# LilypadShield_wPower.net
KiCad netlist of a schematic drawn in EAGLE
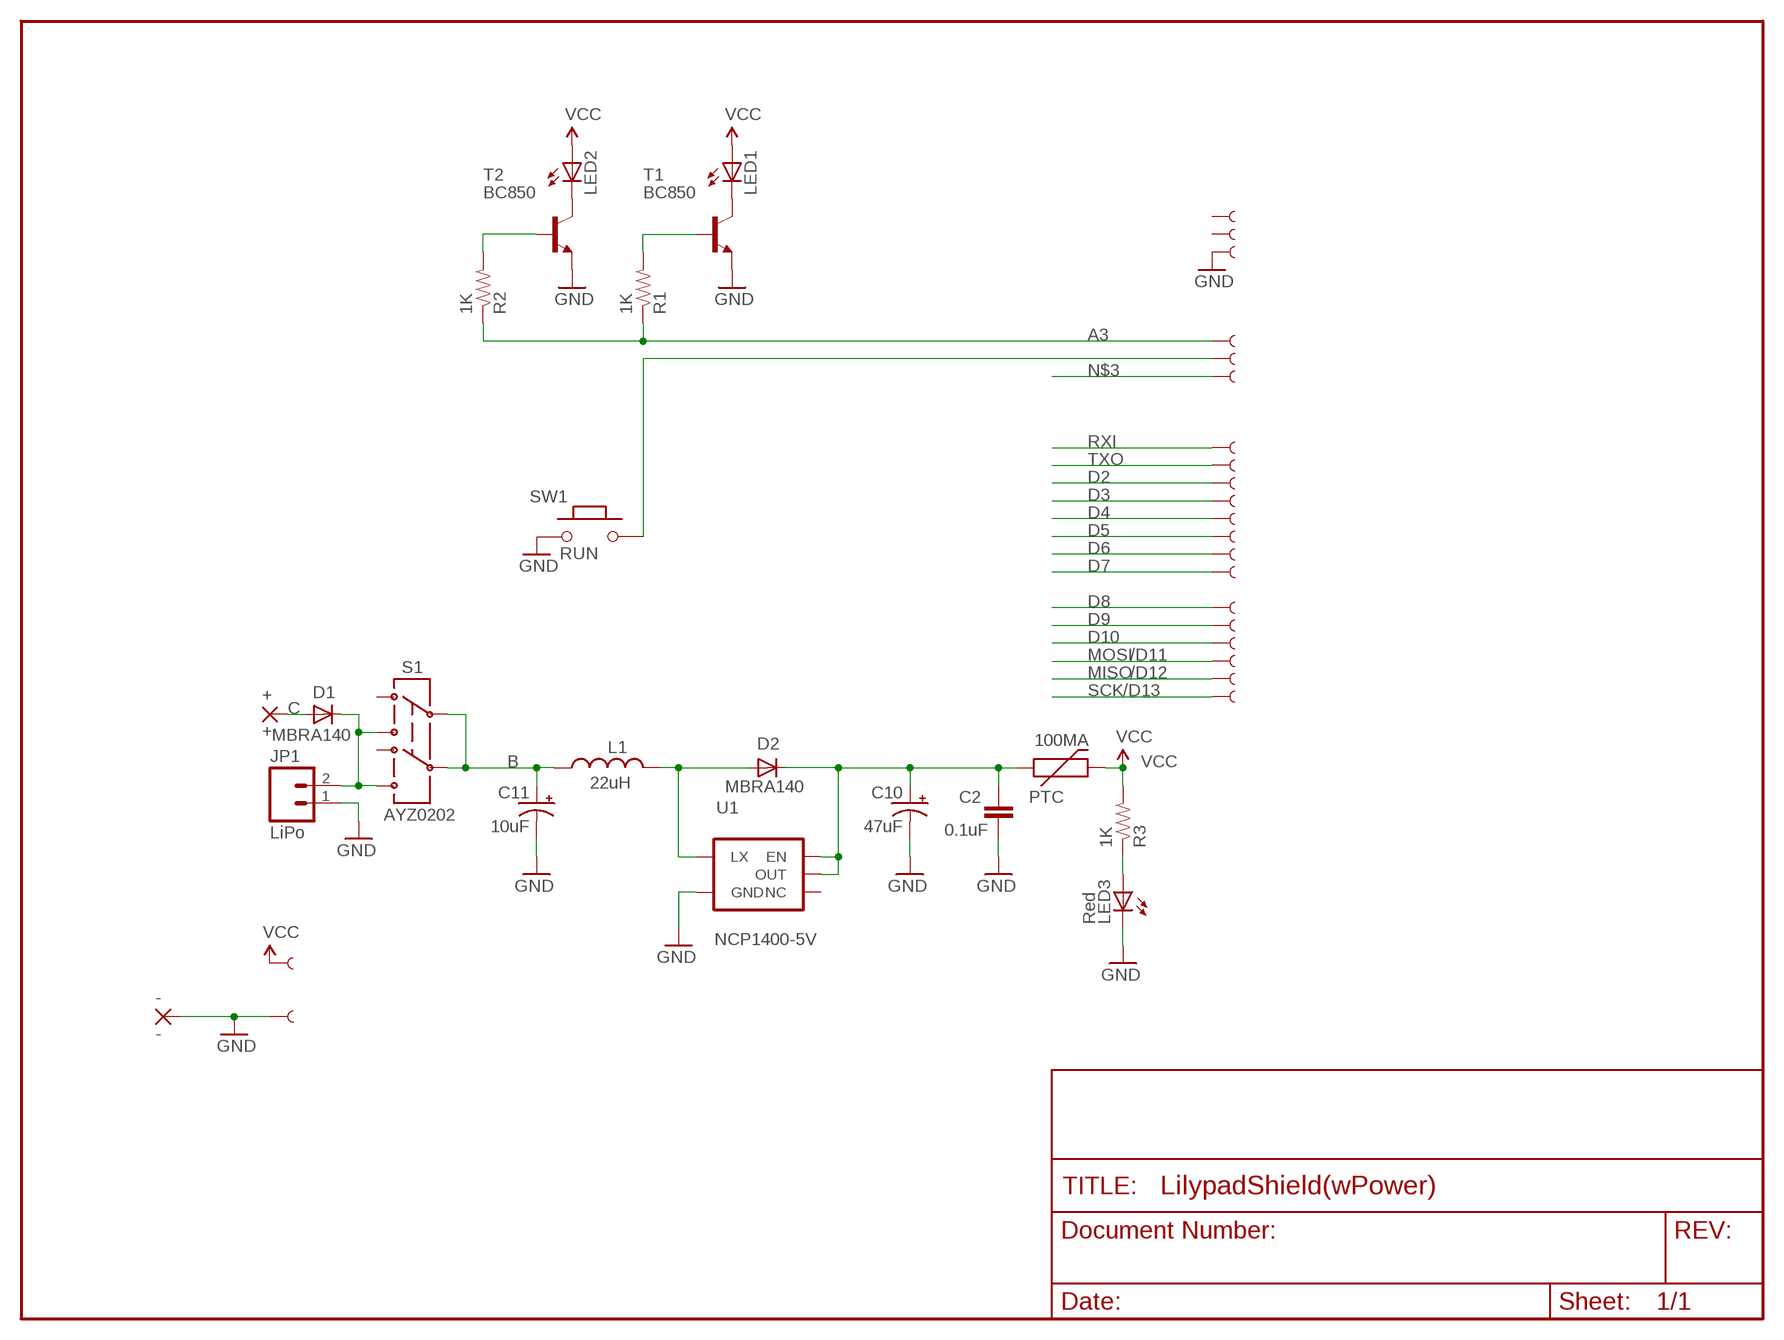
[diagram p0: schematic, sheet 1]

(export (version "E")
  (design (tool "Eeschema 10.0.6"))
  (components
    (comp (ref "+")
      (value "+")
      (footprint "eagle-import:1,6_0,8")
      (libsource (lib "eagle-import") (part "1,6/0,8"))
    )
    (comp (ref "-")
      (value "-")
      (footprint "eagle-import:1,6_0,8")
      (libsource (lib "eagle-import") (part "1,6/0,8"))
    )
    (comp (ref "100MA")
      (value "PTC")
      (footprint "eagle-import:PTC-1206")
      (libsource (lib "eagle-import") (part "PTCSMD"))
    )
    (comp (ref "C2")
      (value "0.1uF")
      (footprint "eagle-import:0603-CAP")
      (libsource (lib "eagle-import") (part "CAP0603-CAP"))
    )
    (comp (ref "C10")
      (value "47uF")
      (footprint "eagle-import:EIA3528-21")
      (libsource (lib "eagle-import") (part "CAP_POL2"))
    )
    (comp (ref "C11")
      (value "10uF")
      (footprint "eagle-import:CPOL_1206")
      (libsource (lib "eagle-import") (part "CAP_POL1206"))
    )
    (comp (ref "D1")
      (value "MBRA140")
      (footprint "eagle-import:SMA-DIODE")
      (libsource (lib "eagle-import") (part "DIODESMA"))
    )
    (comp (ref "D2")
      (value "MBRA140")
      (footprint "eagle-import:SMA-DIODE")
      (libsource (lib "eagle-import") (part "DIODESMA"))
    )
    (comp (ref "GND")
      (value "SEWTAP1")
      (footprint "eagle-import:SEWTAP")
      (libsource (lib "eagle-import") (part "SEWTAP1"))
    )
    (comp (ref "JP1")
      (value "LiPo")
      (footprint "eagle-import:JST-2-SMD")
      (libsource (lib "eagle-import") (part "M02-JST-2MM-SMT"))
    )
    (comp (ref "L1")
      (value "22uH")
      (footprint "eagle-import:CR54")
      (libsource (lib "eagle-import") (part "INDUCTORCR54"))
    )
    (comp (ref "LED1")
      (value "LED5MM")
      (footprint "eagle-import:LED5MM")
      (libsource (lib "eagle-import") (part "led_LED5MM"))
    )
    (comp (ref "LED2")
      (value "LED5MM")
      (footprint "eagle-import:LED5MM")
      (libsource (lib "eagle-import") (part "led_LED5MM"))
    )
    (comp (ref "LED3")
      (value "Red")
      (footprint "eagle-import:LED-1206")
      (libsource (lib "eagle-import") (part "LED1206"))
    )
    (comp (ref "R1")
      (value "1K")
      (footprint "eagle-import:0603-RES")
      (libsource (lib "eagle-import") (part "RESISTOR0603-RES"))
    )
    (comp (ref "R2")
      (value "1K")
      (footprint "eagle-import:0603-RES")
      (libsource (lib "eagle-import") (part "RESISTOR0603-RES"))
    )
    (comp (ref "R3")
      (value "1K")
      (footprint "eagle-import:0603-RES")
      (libsource (lib "eagle-import") (part "RESISTOR0603-RES"))
    )
    (comp (ref "S1")
      (value "AYZ0202")
      (footprint "eagle-import:AYZ0202")
      (libsource (lib "eagle-import") (part "AYZ0202"))
    )
    (comp (ref "SW1")
      (value "RUN")
      (footprint "eagle-import:157SW")
      (libsource (lib "eagle-import") (part "PB157"))
    )
    (comp (ref "T1")
      (value "BC850")
      (footprint "eagle-import:SOT23")
      (libsource (lib "eagle-import") (part "BC850"))
    )
    (comp (ref "T2")
      (value "BC850")
      (footprint "eagle-import:SOT23")
      (libsource (lib "eagle-import") (part "BC850"))
    )
    (comp (ref "U$4")
      (value "SEWTAP1")
      (footprint "eagle-import:SEWTAP")
      (libsource (lib "eagle-import") (part "SEWTAP1"))
    )
    (comp (ref "U$30")
      (value "SEWTAP1")
      (footprint "eagle-import:SEWTAP")
      (libsource (lib "eagle-import") (part "SEWTAP1"))
    )
    (comp (ref "U$31")
      (value "SEWTAP1")
      (footprint "eagle-import:SEWTAP")
      (libsource (lib "eagle-import") (part "SEWTAP1"))
    )
    (comp (ref "U$32")
      (value "SEWTAP1")
      (footprint "eagle-import:SEWTAP")
      (libsource (lib "eagle-import") (part "SEWTAP1"))
    )
    (comp (ref "U$33")
      (value "SEWTAP1")
      (footprint "eagle-import:SEWTAP")
      (libsource (lib "eagle-import") (part "SEWTAP1"))
    )
    (comp (ref "U$34")
      (value "SEWTAP1")
      (footprint "eagle-import:SEWTAP")
      (libsource (lib "eagle-import") (part "SEWTAP1"))
    )
    (comp (ref "U$35")
      (value "SEWTAP1")
      (footprint "eagle-import:SEWTAP")
      (libsource (lib "eagle-import") (part "SEWTAP1"))
    )
    (comp (ref "U$36")
      (value "SEWTAP1")
      (footprint "eagle-import:SEWTAP")
      (libsource (lib "eagle-import") (part "SEWTAP1"))
    )
    (comp (ref "U$37")
      (value "SEWTAP1")
      (footprint "eagle-import:SEWTAP")
      (libsource (lib "eagle-import") (part "SEWTAP1"))
    )
    (comp (ref "U$38")
      (value "SEWTAP1")
      (footprint "eagle-import:SEWTAP")
      (libsource (lib "eagle-import") (part "SEWTAP1"))
    )
    (comp (ref "U$39")
      (value "SEWTAP1")
      (footprint "eagle-import:SEWTAP")
      (libsource (lib "eagle-import") (part "SEWTAP1"))
    )
    (comp (ref "U$40")
      (value "SEWTAP1")
      (footprint "eagle-import:SEWTAP")
      (libsource (lib "eagle-import") (part "SEWTAP1"))
    )
    (comp (ref "U$41")
      (value "SEWTAP1")
      (footprint "eagle-import:SEWTAP")
      (libsource (lib "eagle-import") (part "SEWTAP1"))
    )
    (comp (ref "U$42")
      (value "SEWTAP1")
      (footprint "eagle-import:SEWTAP")
      (libsource (lib "eagle-import") (part "SEWTAP1"))
    )
    (comp (ref "U$43")
      (value "SEWTAP1")
      (footprint "eagle-import:SEWTAP")
      (libsource (lib "eagle-import") (part "SEWTAP1"))
    )
    (comp (ref "U$44")
      (value "SEWTAP1")
      (footprint "eagle-import:SEWTAP")
      (libsource (lib "eagle-import") (part "SEWTAP1"))
    )
    (comp (ref "U$45")
      (value "SEWTAP1")
      (footprint "eagle-import:SEWTAP")
      (libsource (lib "eagle-import") (part "SEWTAP1"))
    )
    (comp (ref "U$46")
      (value "SEWTAP1")
      (footprint "eagle-import:SEWTAP")
      (libsource (lib "eagle-import") (part "SEWTAP1"))
    )
    (comp (ref "U$47")
      (value "SEWTAP1")
      (footprint "eagle-import:SEWTAP")
      (libsource (lib "eagle-import") (part "SEWTAP1"))
    )
    (comp (ref "U$48")
      (value "SEWTAP1")
      (footprint "eagle-import:SEWTAP")
      (libsource (lib "eagle-import") (part "SEWTAP1"))
    )
    (comp (ref "U$51")
      (value "SEWTAP1")
      (footprint "eagle-import:SEWTAP")
      (libsource (lib "eagle-import") (part "SEWTAP1"))
    )
    (comp (ref "U1")
      (value "NCP1400-5V")
      (footprint "eagle-import:SOT23-5")
      (libsource (lib "eagle-import") (part "V_REG_NCP1400SOT23-5"))
    )
  )
  (nets
    (net (code "1") (name "/A3") (class "Default")
      (node (ref "R1") (pin "1") (pinfunction "1_1") (pintype "passive"))
      (node (ref "R2") (pin "1") (pinfunction "1_1") (pintype "passive"))
      (node (ref "U$32") (pin "1") (pinfunction "1_1") (pintype "bidirectional"))
    )
    (net (code "2") (name "/B") (class "Default")
      (node (ref "C11") (pin "A") (pinfunction "+_A") (pintype "passive"))
      (node (ref "L1") (pin "P$2") (pinfunction "2_P$2") (pintype "passive"))
      (node (ref "S1") (pin "2") (pinfunction "2_2") (pintype "bidirectional"))
      (node (ref "S1") (pin "5") (pinfunction "5_5") (pintype "bidirectional"))
    )
    (net (code "3") (name "/C") (class "Default")
      (node (ref "+") (pin "1") (pinfunction "P_1") (pintype "passive"))
      (node (ref "D1") (pin "A") (pinfunction "A_A") (pintype "passive"))
    )
    (net (code "4") (name "/D2") (class "Default")
      (node (ref "U$45") (pin "1") (pinfunction "1_1") (pintype "bidirectional"))
    )
    (net (code "5") (name "/D3") (class "Default")
      (node (ref "U$44") (pin "1") (pinfunction "1_1") (pintype "bidirectional"))
    )
    (net (code "6") (name "/D4") (class "Default")
      (node (ref "U$43") (pin "1") (pinfunction "1_1") (pintype "bidirectional"))
    )
    (net (code "7") (name "/D5") (class "Default")
      (node (ref "U$42") (pin "1") (pinfunction "1_1") (pintype "bidirectional"))
    )
    (net (code "8") (name "/D6") (class "Default")
      (node (ref "U$41") (pin "1") (pinfunction "1_1") (pintype "bidirectional"))
    )
    (net (code "9") (name "/D7") (class "Default")
      (node (ref "U$48") (pin "1") (pinfunction "1_1") (pintype "bidirectional"))
    )
    (net (code "10") (name "/D8") (class "Default")
      (node (ref "U$35") (pin "1") (pinfunction "1_1") (pintype "bidirectional"))
    )
    (net (code "11") (name "/D9") (class "Default")
      (node (ref "U$36") (pin "1") (pinfunction "1_1") (pintype "bidirectional"))
    )
    (net (code "12") (name "/D10") (class "Default")
      (node (ref "U$37") (pin "1") (pinfunction "1_1") (pintype "bidirectional"))
    )
    (net (code "13") (name "/MISO") (class "Default")
      (node (ref "U$39") (pin "1") (pinfunction "1_1") (pintype "bidirectional"))
    )
    (net (code "14") (name "/MOSI") (class "Default")
      (node (ref "U$38") (pin "1") (pinfunction "1_1") (pintype "bidirectional"))
    )
    (net (code "15") (name "/N$3") (class "Default")
      (node (ref "U$34") (pin "1") (pinfunction "1_1") (pintype "bidirectional"))
    )
    (net (code "16") (name "/RXI") (class "Default")
      (node (ref "U$47") (pin "1") (pinfunction "1_1") (pintype "bidirectional"))
    )
    (net (code "17") (name "/SCK") (class "Default")
      (node (ref "U$40") (pin "1") (pinfunction "1_1") (pintype "bidirectional"))
    )
    (net (code "18") (name "/TXO") (class "Default")
      (node (ref "U$46") (pin "1") (pinfunction "1_1") (pintype "bidirectional"))
    )
    (net (code "19") (name "GND") (class "Default")
      (node (ref "-") (pin "1") (pinfunction "P_1") (pintype "passive"))
      (node (ref "C10") (pin "C") (pinfunction "-_C") (pintype "passive"))
      (node (ref "C11") (pin "C") (pinfunction "-_C") (pintype "passive"))
      (node (ref "C2") (pin "2") (pinfunction "2_2") (pintype "passive"))
      (node (ref "JP1") (pin "1") (pinfunction "1_1") (pintype "passive"))
      (node (ref "LED3") (pin "C") (pinfunction "C_C") (pintype "passive"))
      (node (ref "SW1") (pin "1") (pinfunction "1_1") (pintype "passive"))
      (node (ref "T1") (pin "2") (pinfunction "E_2") (pintype "passive"))
      (node (ref "T2") (pin "2") (pinfunction "E_2") (pintype "passive"))
      (node (ref "U$30") (pin "1") (pinfunction "1_1") (pintype "bidirectional"))
      (node (ref "U$31") (pin "1") (pinfunction "1_1") (pintype "bidirectional"))
      (node (ref "U1") (pin "4") (pinfunction "GND_4") (pintype "input"))
    )
    (net (code "20") (name "Net-(C10-+)") (class "Default")
      (node (ref "100MA") (pin "1") (pinfunction "1_1") (pintype "bidirectional"))
      (node (ref "C10") (pin "A") (pinfunction "+_A") (pintype "passive"))
      (node (ref "C2") (pin "1") (pinfunction "1_1") (pintype "passive"))
      (node (ref "D2") (pin "C") (pinfunction "C_C") (pintype "passive"))
      (node (ref "U1") (pin "1") (pinfunction "EN_1") (pintype "input"))
      (node (ref "U1") (pin "2") (pinfunction "OUT_2") (pintype "passive"))
    )
    (net (code "21") (name "Net-(L1-1)") (class "Default")
      (node (ref "D2") (pin "A") (pinfunction "A_A") (pintype "passive"))
      (node (ref "L1") (pin "P$1") (pinfunction "1_P$1") (pintype "passive"))
      (node (ref "U1") (pin "5") (pinfunction "LX_5") (pintype "input"))
    )
    (net (code "22") (name "Net-(LED1-C)") (class "Default")
      (node (ref "LED1") (pin "K") (pinfunction "C_K") (pintype "passive"))
      (node (ref "T1") (pin "3") (pinfunction "C_3") (pintype "passive"))
    )
    (net (code "23") (name "Net-(LED2-C)") (class "Default")
      (node (ref "LED2") (pin "K") (pinfunction "C_K") (pintype "passive"))
      (node (ref "T2") (pin "3") (pinfunction "C_3") (pintype "passive"))
    )
    (net (code "24") (name "Net-(LED3-PadA)") (class "Default")
      (node (ref "LED3") (pin "A") (pinfunction "A_A") (pintype "passive"))
      (node (ref "R3") (pin "1") (pinfunction "1_1") (pintype "passive"))
    )
    (net (code "25") (name "Net-(S1-3)") (class "Default")
      (node (ref "D1") (pin "C") (pinfunction "C_C") (pintype "passive"))
      (node (ref "JP1") (pin "2") (pinfunction "2_2") (pintype "passive"))
      (node (ref "S1") (pin "1") (pinfunction "3_1") (pintype "bidirectional"))
      (node (ref "S1") (pin "4") (pinfunction "6_4") (pintype "bidirectional"))
    )
    (net (code "26") (name "Net-(SW1-Pad2)") (class "Default")
      (node (ref "SW1") (pin "2") (pinfunction "2_2") (pintype "passive"))
      (node (ref "U$33") (pin "1") (pinfunction "1_1") (pintype "bidirectional"))
    )
    (net (code "27") (name "Net-(T1-B)") (class "Default")
      (node (ref "R1") (pin "2") (pinfunction "2_2") (pintype "passive"))
      (node (ref "T1") (pin "1") (pinfunction "B_1") (pintype "passive"))
    )
    (net (code "28") (name "Net-(T2-B)") (class "Default")
      (node (ref "R2") (pin "2") (pinfunction "2_2") (pintype "passive"))
      (node (ref "T2") (pin "1") (pinfunction "B_1") (pintype "passive"))
    )
    (net (code "29") (name "VCC") (class "Default")
      (node (ref "100MA") (pin "2") (pinfunction "2_2") (pintype "bidirectional"))
      (node (ref "LED1") (pin "A") (pinfunction "A_A") (pintype "passive"))
      (node (ref "LED2") (pin "A") (pinfunction "A_A") (pintype "passive"))
      (node (ref "R3") (pin "2") (pinfunction "2_2") (pintype "passive"))
      (node (ref "U$4") (pin "1") (pinfunction "1_1") (pintype "bidirectional"))
    )
    (net (code "30") (name "unconnected-(GND-Pad1)") (class "Default")
      (node (ref "GND") (pin "1") (pinfunction "1_1") (pintype "bidirectional"))
    )
    (net (code "31") (name "unconnected-(S1-1-Pad3)") (class "Default")
      (node (ref "S1") (pin "3") (pinfunction "1_3") (pintype "bidirectional"))
    )
    (net (code "32") (name "unconnected-(S1-4-Pad6)") (class "Default")
      (node (ref "S1") (pin "6") (pinfunction "4_6") (pintype "bidirectional"))
    )
    (net (code "33") (name "unconnected-(U$51-Pad1)") (class "Default")
      (node (ref "U$51") (pin "1") (pinfunction "1_1") (pintype "bidirectional"))
    )
    (net (code "34") (name "unconnected-(U1-NC-Pad3)") (class "Default")
      (node (ref "U1") (pin "3") (pinfunction "NC_3") (pintype "input"))
    )
  )
)
